# STM32_microcontroller_power.net
KiCad netlist of a schematic drawn in Altium Designer
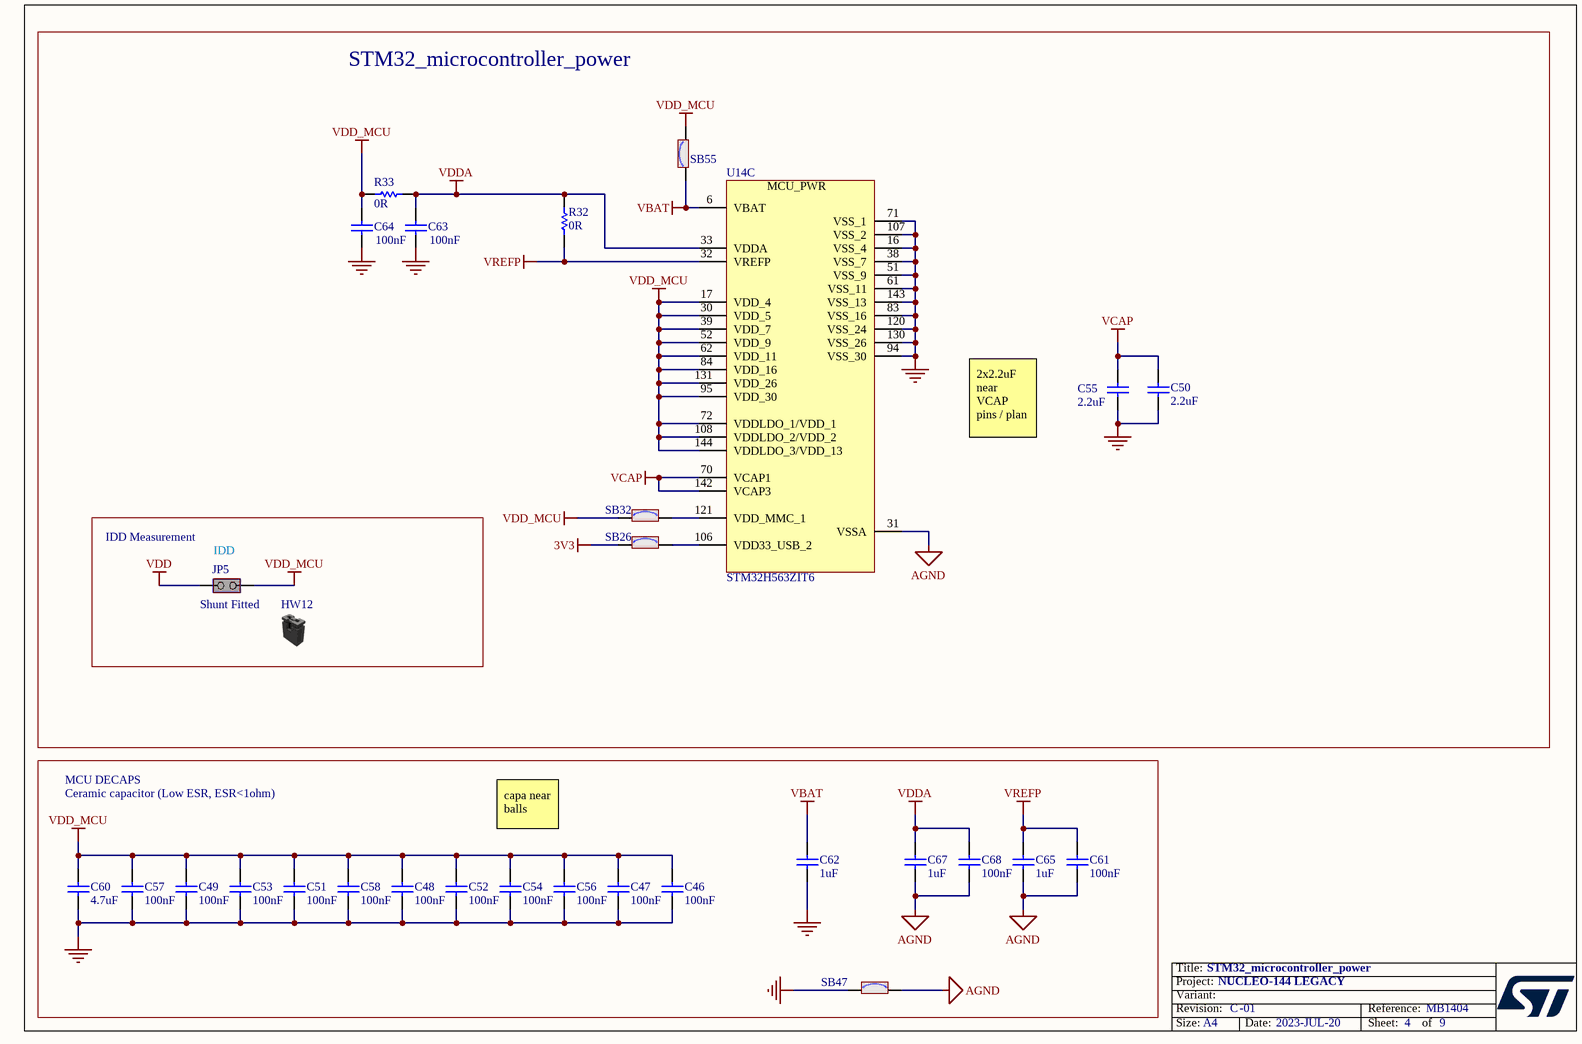
[diagram p0: STM32_microcontroller_power.SchDoc]

(export (version "E")
  (design (tool "Eeschema 10.0.6"))
  (components
    (comp (ref "C46")
      (value "100nF")
      (footprint "MCD_PARTS:C0402")
      (description "Capacitor, MLCC, 100nF, 16V, X7R, +/-10%, 0402, T=0.5mm")
      (fields (field (name "INTERNAL_PART_NUMBER") "MCD-00006") (field (name "MANUFACTURER") "YAGEO"))
      (libsource (lib "MCD_PARTS_database") (part "Capacitor"))
    )
    (comp (ref "C47")
      (value "100nF")
      (footprint "MCD_PARTS:C0402")
      (description "Capacitor, MLCC, 100nF, 16V, X7R, +/-10%, 0402, T=0.5mm")
      (fields (field (name "INTERNAL_PART_NUMBER") "MCD-00006") (field (name "MANUFACTURER") "YAGEO"))
      (libsource (lib "MCD_PARTS_database") (part "Capacitor"))
    )
    (comp (ref "C48")
      (value "100nF")
      (footprint "MCD_PARTS:C0402")
      (description "Capacitor, MLCC, 100nF, 16V, X7R, +/-10%, 0402, T=0.5mm")
      (fields (field (name "INTERNAL_PART_NUMBER") "MCD-00006") (field (name "MANUFACTURER") "YAGEO"))
      (libsource (lib "MCD_PARTS_database") (part "Capacitor"))
    )
    (comp (ref "C49")
      (value "100nF")
      (footprint "MCD_PARTS:C0402")
      (description "Capacitor, MLCC, 100nF, 16V, X7R, +/-10%, 0402, T=0.5mm")
      (fields (field (name "INTERNAL_PART_NUMBER") "MCD-00006") (field (name "MANUFACTURER") "YAGEO"))
      (libsource (lib "MCD_PARTS_database") (part "Capacitor"))
    )
    (comp (ref "C50")
      (value "2.2uF")
      (footprint "MCD_PARTS:C0603")
      (description "Capacitor, MLCC, 2.2uF, 10V, X5R, 10%, 0603, T=0,8mm")
      (fields
        (field (name "INTERNAL_PART_NUMBER") "MCD-00012")
        (field (name "MANUFACTURER_PART_NUMBER") "CC0603KRX5R6BB225")
        (field (name "PROVIDED_BY") "SUBCO")
      )
      (libsource (lib "MCD_PARTS_database") (part "Capacitor"))
    )
    (comp (ref "C51")
      (value "100nF")
      (footprint "MCD_PARTS:C0402")
      (description "Capacitor, MLCC, 100nF, 16V, X7R, +/-10%, 0402, T=0.5mm")
      (fields (field (name "INTERNAL_PART_NUMBER") "MCD-00006") (field (name "MANUFACTURER") "YAGEO"))
      (libsource (lib "MCD_PARTS_database") (part "Capacitor"))
    )
    (comp (ref "C52")
      (value "100nF")
      (footprint "MCD_PARTS:C0402")
      (description "Capacitor, MLCC, 100nF, 16V, X7R, +/-10%, 0402, T=0.5mm")
      (fields (field (name "INTERNAL_PART_NUMBER") "MCD-00006") (field (name "MANUFACTURER") "YAGEO"))
      (libsource (lib "MCD_PARTS_database") (part "Capacitor"))
    )
    (comp (ref "C53")
      (value "100nF")
      (footprint "MCD_PARTS:C0402")
      (description "Capacitor, MLCC, 100nF, 16V, X7R, +/-10%, 0402, T=0.5mm")
      (fields (field (name "INTERNAL_PART_NUMBER") "MCD-00006") (field (name "MANUFACTURER") "YAGEO"))
      (libsource (lib "MCD_PARTS_database") (part "Capacitor"))
    )
    (comp (ref "C54")
      (value "100nF")
      (footprint "MCD_PARTS:C0402")
      (description "Capacitor, MLCC, 100nF, 16V, X7R, +/-10%, 0402, T=0.5mm")
      (fields (field (name "INTERNAL_PART_NUMBER") "MCD-00006") (field (name "MANUFACTURER") "YAGEO"))
      (libsource (lib "MCD_PARTS_database") (part "Capacitor"))
    )
    (comp (ref "C55")
      (value "2.2uF")
      (footprint "MCD_PARTS:C0603")
      (description "Capacitor, MLCC, 2.2uF, 10V, X5R, 10%, 0603, T=0,8mm")
      (fields
        (field (name "INTERNAL_PART_NUMBER") "MCD-00012")
        (field (name "MANUFACTURER_PART_NUMBER") "CC0603KRX5R6BB225")
        (field (name "PROVIDED_BY") "SUBCO")
      )
      (libsource (lib "MCD_PARTS_database") (part "Capacitor"))
    )
    (comp (ref "C56")
      (value "100nF")
      (footprint "MCD_PARTS:C0402")
      (description "Capacitor, MLCC, 100nF, 16V, X7R, +/-10%, 0402, T=0.5mm")
      (fields (field (name "INTERNAL_PART_NUMBER") "MCD-00006") (field (name "MANUFACTURER") "YAGEO"))
      (libsource (lib "MCD_PARTS_database") (part "Capacitor"))
    )
    (comp (ref "C57")
      (value "100nF")
      (footprint "MCD_PARTS:C0402")
      (description "Capacitor, MLCC, 100nF, 16V, X7R, +/-10%, 0402, T=0.5mm")
      (fields (field (name "INTERNAL_PART_NUMBER") "MCD-00006") (field (name "MANUFACTURER") "YAGEO"))
      (libsource (lib "MCD_PARTS_database") (part "Capacitor"))
    )
    (comp (ref "C58")
      (value "100nF")
      (footprint "MCD_PARTS:C0402")
      (description "Capacitor, MLCC, 100nF, 16V, X7R, +/-10%, 0402, T=0.5mm")
      (fields (field (name "INTERNAL_PART_NUMBER") "MCD-00006") (field (name "MANUFACTURER") "YAGEO"))
      (libsource (lib "MCD_PARTS_database") (part "Capacitor"))
    )
    (comp (ref "C60")
      (value "4.7uF")
      (footprint "C0603_H0P8")
      (description "Capacitor, MLCC, 4.7uF, 10V, X5R, +/-20%, 0603, T=0.8mm")
      (fields (field (name "INTERNAL_PART_NUMBER") "MCD-03342") (field (name "MANUFACTURER") "YAGEO"))
      (libsource (lib "MCD_PARTS_database") (part "Capacitor"))
    )
    (comp (ref "C61")
      (value "100nF")
      (footprint "MCD_PARTS:C0402")
      (description "Capacitor, MLCC, 100nF, 16V, X7R, +/-10%, 0402, T=0.5mm")
      (fields (field (name "INTERNAL_PART_NUMBER") "MCD-00006") (field (name "MANUFACTURER") "YAGEO"))
      (libsource (lib "MCD_PARTS_database") (part "Capacitor"))
    )
    (comp (ref "C62")
      (value "1uF")
      (footprint "MCD_PARTS:C0603")
      (description "Capacitor, MLCC, 1uF, 6V3, X5R, 10%, 0603, T=0,8mm")
      (fields
        (field (name "INTERNAL_PART_NUMBER") "MCD-00238")
        (field (name "MANUFACTURER_PART_NUMBER") "CC0603KRX5R5BB105")
        (field (name "PROVIDED_BY") "SUBCO")
      )
      (libsource (lib "MCD_PARTS_database") (part "Capacitor"))
    )
    (comp (ref "C63")
      (value "100nF")
      (footprint "MCD_PARTS:C0402")
      (description "Capacitor, MLCC, 100nF, 16V, X7R, 10%, 0402, T=0.5mm")
      (fields
        (field (name "INTERNAL_PART_NUMBER") "MCD-00006")
        (field (name "MANUFACTURER_PART_NUMBER") "CC0402KRX7R7BB104")
        (field (name "PROVIDED_BY") "SUBCO")
      )
      (libsource (lib "MCD_PARTS_database") (part "Capacitor"))
    )
    (comp (ref "C64")
      (value "100nF")
      (footprint "MCD_PARTS:C0402")
      (description "Capacitor, MLCC, 100nF, 16V, X7R, 10%, 0402, T=0.5mm")
      (fields
        (field (name "INTERNAL_PART_NUMBER") "MCD-00006")
        (field (name "MANUFACTURER_PART_NUMBER") "CC0402KRX7R7BB104")
        (field (name "PROVIDED_BY") "SUBCO")
      )
      (libsource (lib "MCD_PARTS_database") (part "Capacitor"))
    )
    (comp (ref "C65")
      (value "1uF")
      (footprint "MCD_PARTS:C0603")
      (description "Capacitor, MLCC, 1uF, 6V3, X5R, 10%, 0603, T=0,8mm")
      (fields
        (field (name "INTERNAL_PART_NUMBER") "MCD-00238")
        (field (name "MANUFACTURER_PART_NUMBER") "CC0603KRX5R5BB105")
        (field (name "PROVIDED_BY") "SUBCO")
      )
      (libsource (lib "MCD_PARTS_database") (part "Capacitor"))
    )
    (comp (ref "C67")
      (value "1uF")
      (footprint "MCD_PARTS:C0603")
      (description "Capacitor, MLCC, 1uF, 6V3, X5R, 10%, 0603, T=0,8mm")
      (fields
        (field (name "INTERNAL_PART_NUMBER") "MCD-00238")
        (field (name "MANUFACTURER_PART_NUMBER") "CC0603KRX5R5BB105")
        (field (name "PROVIDED_BY") "SUBCO")
      )
      (libsource (lib "MCD_PARTS_database") (part "Capacitor"))
    )
    (comp (ref "C68")
      (value "100nF")
      (footprint "MCD_PARTS:C0402")
      (description "Capacitor, MLCC, 100nF, 16V, X7R, +/-10%, 0402, T=0.5mm")
      (fields (field (name "INTERNAL_PART_NUMBER") "MCD-00006") (field (name "MANUFACTURER") "YAGEO"))
      (libsource (lib "MCD_PARTS_database") (part "Capacitor"))
    )
    (comp (ref "HW12")
      (value "Shunt Black 2.54mm")
      (description "SHUNT 2.54mm BLACK")
      (fields
        (field (name "INTERNAL_PART_NUMBER") "MCD-00043")
        (field (name "MANUFACTURER_PART_NUMBER") "SNT-100-BK-G")
        (field (name "PROVIDED_BY") "SUBCO")
      )
      (libsource (lib "MCD_PARTS_database") (part "Shunt Black 2.54mm"))
    )
    (comp (ref "JP5")
      (value "Shunt Fitted")
      (footprint "MCD_PARTS:CON_SAMTEC_TSW-102-07-G-S")
      (description "Header, 2x1, 2,54mm, VR, TH, Height 5.84mm/2.54mm - Shunt Fitted by default")
      (fields
        (field (name "INTERNAL_PART_NUMBER") "MCD-00683")
        (field (name "MANUFACTURER_PART_NUMBER") "TSW-102-07-x-S")
        (field (name "PROVIDED_BY") "SUBCO")
      )
      (libsource (lib "MCD_PARTS_database") (part "Jumper_Header 2x1 Fitted"))
    )
    (comp (ref "R32")
      (value "0R")
      (footprint "MCD_PARTS:R0603")
      (description "Resistor,0R,0603,5%,1/10W")
      (fields
        (field (name "INTERNAL_PART_NUMBER") "MCD-00056")
        (field (name "MANUFACTURER_PART_NUMBER") "RC0603JR-070RL")
        (field (name "PROVIDED_BY") "SUBCO")
      )
      (libsource (lib "MCD_PARTS_database") (part "Resistor"))
    )
    (comp (ref "R33")
      (value "0R")
      (footprint "MCD_PARTS:R0603")
      (description "Resistor,0R,0603,5%,1/10W")
      (fields
        (field (name "INTERNAL_PART_NUMBER") "MCD-00056")
        (field (name "MANUFACTURER_PART_NUMBER") "RC0603JR-070RL")
        (field (name "PROVIDED_BY") "SUBCO")
      )
      (libsource (lib "MCD_PARTS_database") (part "Resistor"))
    )
    (comp (ref "SB26")
      (value "SB_ON")
      (footprint "MCD_PARTS:SOLDER-BRIDGE_R0402-0R")
      (description "Solder Bridge 0402 ON")
      (fields
        (field (name "INTERNAL_PART_NUMBER") "MCD-01618")
        (field (name "MANUFACTURER_PART_NUMBER") "RC0402JR-070RL")
        (field (name "PROVIDED_BY") "SUBCO")
      )
      (libsource (lib "") (part "SB_ON_1"))
    )
    (comp (ref "SB32")
      (value "SB_ON")
      (footprint "MCD_PARTS:SOLDER-BRIDGE_R0603-0R")
      (description "Solder Bridge ON")
      (fields
        (field (name "INTERNAL_PART_NUMBER") "MCD-00071")
        (field (name "MANUFACTURER_PART_NUMBER") "RC0603JR-070RL")
        (field (name "PROVIDED_BY") "SUBCO")
      )
      (libsource (lib "") (part "SB_ON_1"))
    )
    (comp (ref "SB47")
      (value "SB_ON")
      (footprint "MCD_PARTS:SOLDER-BRIDGE_R0603-0R")
      (description "Solder Bridge ON")
      (fields
        (field (name "INTERNAL_PART_NUMBER") "MCD-00071")
        (field (name "MANUFACTURER_PART_NUMBER") "RC0603JR-070RL")
        (field (name "PROVIDED_BY") "SUBCO")
      )
      (libsource (lib "") (part "SB_ON_1"))
    )
    (comp (ref "SB55")
      (value "SB_ON")
      (footprint "MCD_PARTS:SOLDER-BRIDGE_R0402-0R")
      (description "Solder Bridge 0402 ON")
      (fields
        (field (name "INTERNAL_PART_NUMBER") "MCD-01618")
        (field (name "MANUFACTURER_PART_NUMBER") "RC0402JR-070RL")
        (field (name "PROVIDED_BY") "SUBCO")
      )
      (libsource (lib "MCD_PARTS_database") (part "SB_ON"))
    )
    (comp (ref "U14")
      (value "STM32H563ZIT6")
      (footprint "MCD_PARTS:ICC_LQFP144_20X20_P050_SOCKET_YAMAICHI_IC149-144-145-B5_NM")
      (description "STM32H563ZIT6, LQFP144 package, 20x20")
      (fields
        (field (name "INTERNAL_PART_NUMBER") "MCD-02359")
        (field (name "MANUFACTURER") "STMICROELECTRONICS")
      )
      (libsource (lib "MCD_PARTS_database") (part "STM32H563ZIT6"))
    )
  )
  (nets
    (net (code "1") (name "3V3") (class "Default")
      (node (ref "SB26") (pin "1") (pinfunction "1_1") (pintype "passive"))
    )
    (net (code "2") (name "AGND") (class "Default")
      (node (ref "C61") (pin "1") (pinfunction "1_1") (pintype "passive"))
      (node (ref "C65") (pin "2") (pinfunction "2_2") (pintype "passive"))
      (node (ref "C67") (pin "2") (pinfunction "2_2") (pintype "passive"))
      (node (ref "C68") (pin "1") (pinfunction "1_1") (pintype "passive"))
      (node (ref "SB47") (pin "2") (pinfunction "2_2") (pintype "passive"))
      (node (ref "U14") (pin "31") (pinfunction "VSSA_31") (pintype "passive"))
    )
    (net (code "3") (name "GND") (class "Default")
      (node (ref "C46") (pin "1") (pinfunction "1_1") (pintype "passive"))
      (node (ref "C47") (pin "1") (pinfunction "1_1") (pintype "passive"))
      (node (ref "C48") (pin "1") (pinfunction "1_1") (pintype "passive"))
      (node (ref "C49") (pin "1") (pinfunction "1_1") (pintype "passive"))
      (node (ref "C50") (pin "1") (pinfunction "1_1") (pintype "passive"))
      (node (ref "C51") (pin "1") (pinfunction "1_1") (pintype "passive"))
      (node (ref "C52") (pin "1") (pinfunction "1_1") (pintype "passive"))
      (node (ref "C53") (pin "1") (pinfunction "1_1") (pintype "passive"))
      (node (ref "C54") (pin "1") (pinfunction "1_1") (pintype "passive"))
      (node (ref "C55") (pin "1") (pinfunction "1_1") (pintype "passive"))
      (node (ref "C56") (pin "1") (pinfunction "1_1") (pintype "passive"))
      (node (ref "C57") (pin "1") (pinfunction "1_1") (pintype "passive"))
      (node (ref "C58") (pin "1") (pinfunction "1_1") (pintype "passive"))
      (node (ref "C60") (pin "1") (pinfunction "1_1") (pintype "passive"))
      (node (ref "C62") (pin "1") (pinfunction "1_1") (pintype "passive"))
      (node (ref "C63") (pin "2") (pinfunction "2_2") (pintype "passive"))
      (node (ref "C64") (pin "2") (pinfunction "2_2") (pintype "passive"))
      (node (ref "SB47") (pin "1") (pinfunction "1_1") (pintype "passive"))
      (node (ref "U14") (pin "107") (pinfunction "VSS_2_107") (pintype "passive"))
      (node (ref "U14") (pin "120") (pinfunction "VSS_24_120") (pintype "passive"))
      (node (ref "U14") (pin "130") (pinfunction "VSS_26_130") (pintype "passive"))
      (node (ref "U14") (pin "143") (pinfunction "VSS_13_143") (pintype "passive"))
      (node (ref "U14") (pin "16") (pinfunction "VSS_4_16") (pintype "passive"))
      (node (ref "U14") (pin "38") (pinfunction "VSS_7_38") (pintype "passive"))
      (node (ref "U14") (pin "51") (pinfunction "VSS_9_51") (pintype "passive"))
      (node (ref "U14") (pin "61") (pinfunction "VSS_11_61") (pintype "passive"))
      (node (ref "U14") (pin "71") (pinfunction "VSS_1_71") (pintype "passive"))
      (node (ref "U14") (pin "83") (pinfunction "VSS_16_83") (pintype "passive"))
      (node (ref "U14") (pin "94") (pinfunction "VSS_30_94") (pintype "passive"))
    )
    (net (code "4") (name "Net-(U14C-VDD33_USB_2)") (class "Default")
      (node (ref "SB26") (pin "2") (pinfunction "2_2") (pintype "passive"))
      (node (ref "U14") (pin "106") (pinfunction "VDD33_USB_2_106") (pintype "passive"))
    )
    (net (code "5") (name "Net-(U14C-VDD_MMC_1)") (class "Default")
      (node (ref "SB32") (pin "2") (pinfunction "2_2") (pintype "passive"))
      (node (ref "U14") (pin "121") (pinfunction "VDD_MMC_1_121") (pintype "passive"))
    )
    (net (code "6") (name "VBAT") (class "Default")
      (node (ref "C62") (pin "2") (pinfunction "2_2") (pintype "passive"))
      (node (ref "SB55") (pin "1") (pinfunction "1_1") (pintype "passive"))
      (node (ref "U14") (pin "6") (pinfunction "VBAT_6") (pintype "passive"))
    )
    (net (code "7") (name "VCAP") (class "Default")
      (node (ref "C50") (pin "2") (pinfunction "2_2") (pintype "passive"))
      (node (ref "C55") (pin "2") (pinfunction "2_2") (pintype "passive"))
      (node (ref "U14") (pin "142") (pinfunction "VCAP3_142") (pintype "passive"))
      (node (ref "U14") (pin "70") (pinfunction "VCAP1_70") (pintype "passive"))
    )
    (net (code "8") (name "VDD") (class "Default")
      (node (ref "JP5") (pin "1") (pinfunction "COMMON_1") (pintype "passive"))
    )
    (net (code "9") (name "VDDA") (class "Default")
      (node (ref "C63") (pin "1") (pinfunction "1_1") (pintype "passive"))
      (node (ref "C67") (pin "1") (pinfunction "1_1") (pintype "passive"))
      (node (ref "C68") (pin "2") (pinfunction "2_2") (pintype "passive"))
      (node (ref "R32") (pin "1") (pinfunction "1_1") (pintype "passive"))
      (node (ref "R33") (pin "2") (pinfunction "2_2") (pintype "passive"))
      (node (ref "U14") (pin "33") (pinfunction "VDDA_33") (pintype "passive"))
    )
    (net (code "10") (name "VDD_MCU") (class "Default")
      (node (ref "C46") (pin "2") (pinfunction "2_2") (pintype "passive"))
      (node (ref "C47") (pin "2") (pinfunction "2_2") (pintype "passive"))
      (node (ref "C48") (pin "2") (pinfunction "2_2") (pintype "passive"))
      (node (ref "C49") (pin "2") (pinfunction "2_2") (pintype "passive"))
      (node (ref "C51") (pin "2") (pinfunction "2_2") (pintype "passive"))
      (node (ref "C52") (pin "2") (pinfunction "2_2") (pintype "passive"))
      (node (ref "C53") (pin "2") (pinfunction "2_2") (pintype "passive"))
      (node (ref "C54") (pin "2") (pinfunction "2_2") (pintype "passive"))
      (node (ref "C56") (pin "2") (pinfunction "2_2") (pintype "passive"))
      (node (ref "C57") (pin "2") (pinfunction "2_2") (pintype "passive"))
      (node (ref "C58") (pin "2") (pinfunction "2_2") (pintype "passive"))
      (node (ref "C60") (pin "2") (pinfunction "2_2") (pintype "passive"))
      (node (ref "C64") (pin "1") (pinfunction "1_1") (pintype "passive"))
      (node (ref "JP5") (pin "2") (pinfunction "NO_2") (pintype "passive"))
      (node (ref "R33") (pin "1") (pinfunction "1_1") (pintype "passive"))
      (node (ref "SB32") (pin "1") (pinfunction "1_1") (pintype "passive"))
      (node (ref "SB55") (pin "2") (pinfunction "2_2") (pintype "passive"))
      (node (ref "U14") (pin "108") (pinfunction "VDDLDO_2/VDD_2_108") (pintype "passive"))
      (node (ref "U14") (pin "131") (pinfunction "VDD_26_131") (pintype "passive"))
      (node (ref "U14") (pin "144") (pinfunction "VDDLDO_3/VDD_13_144") (pintype "passive"))
      (node (ref "U14") (pin "17") (pinfunction "VDD_4_17") (pintype "passive"))
      (node (ref "U14") (pin "30") (pinfunction "VDD_5_30") (pintype "passive"))
      (node (ref "U14") (pin "39") (pinfunction "VDD_7_39") (pintype "passive"))
      (node (ref "U14") (pin "52") (pinfunction "VDD_9_52") (pintype "passive"))
      (node (ref "U14") (pin "62") (pinfunction "VDD_11_62") (pintype "passive"))
      (node (ref "U14") (pin "72") (pinfunction "VDDLDO_1/VDD_1_72") (pintype "passive"))
      (node (ref "U14") (pin "84") (pinfunction "VDD_16_84") (pintype "passive"))
      (node (ref "U14") (pin "95") (pinfunction "VDD_30_95") (pintype "passive"))
    )
    (net (code "11") (name "VREFP") (class "Default")
      (node (ref "C61") (pin "2") (pinfunction "2_2") (pintype "passive"))
      (node (ref "C65") (pin "1") (pinfunction "1_1") (pintype "passive"))
      (node (ref "R32") (pin "2") (pinfunction "2_2") (pintype "passive"))
      (node (ref "U14") (pin "32") (pinfunction "VREFP_32") (pintype "passive"))
    )
  )
)
